# RejsaCAN_v6_0_-_Schematic.net
KiCad netlist of a schematic drawn in EasyEDA
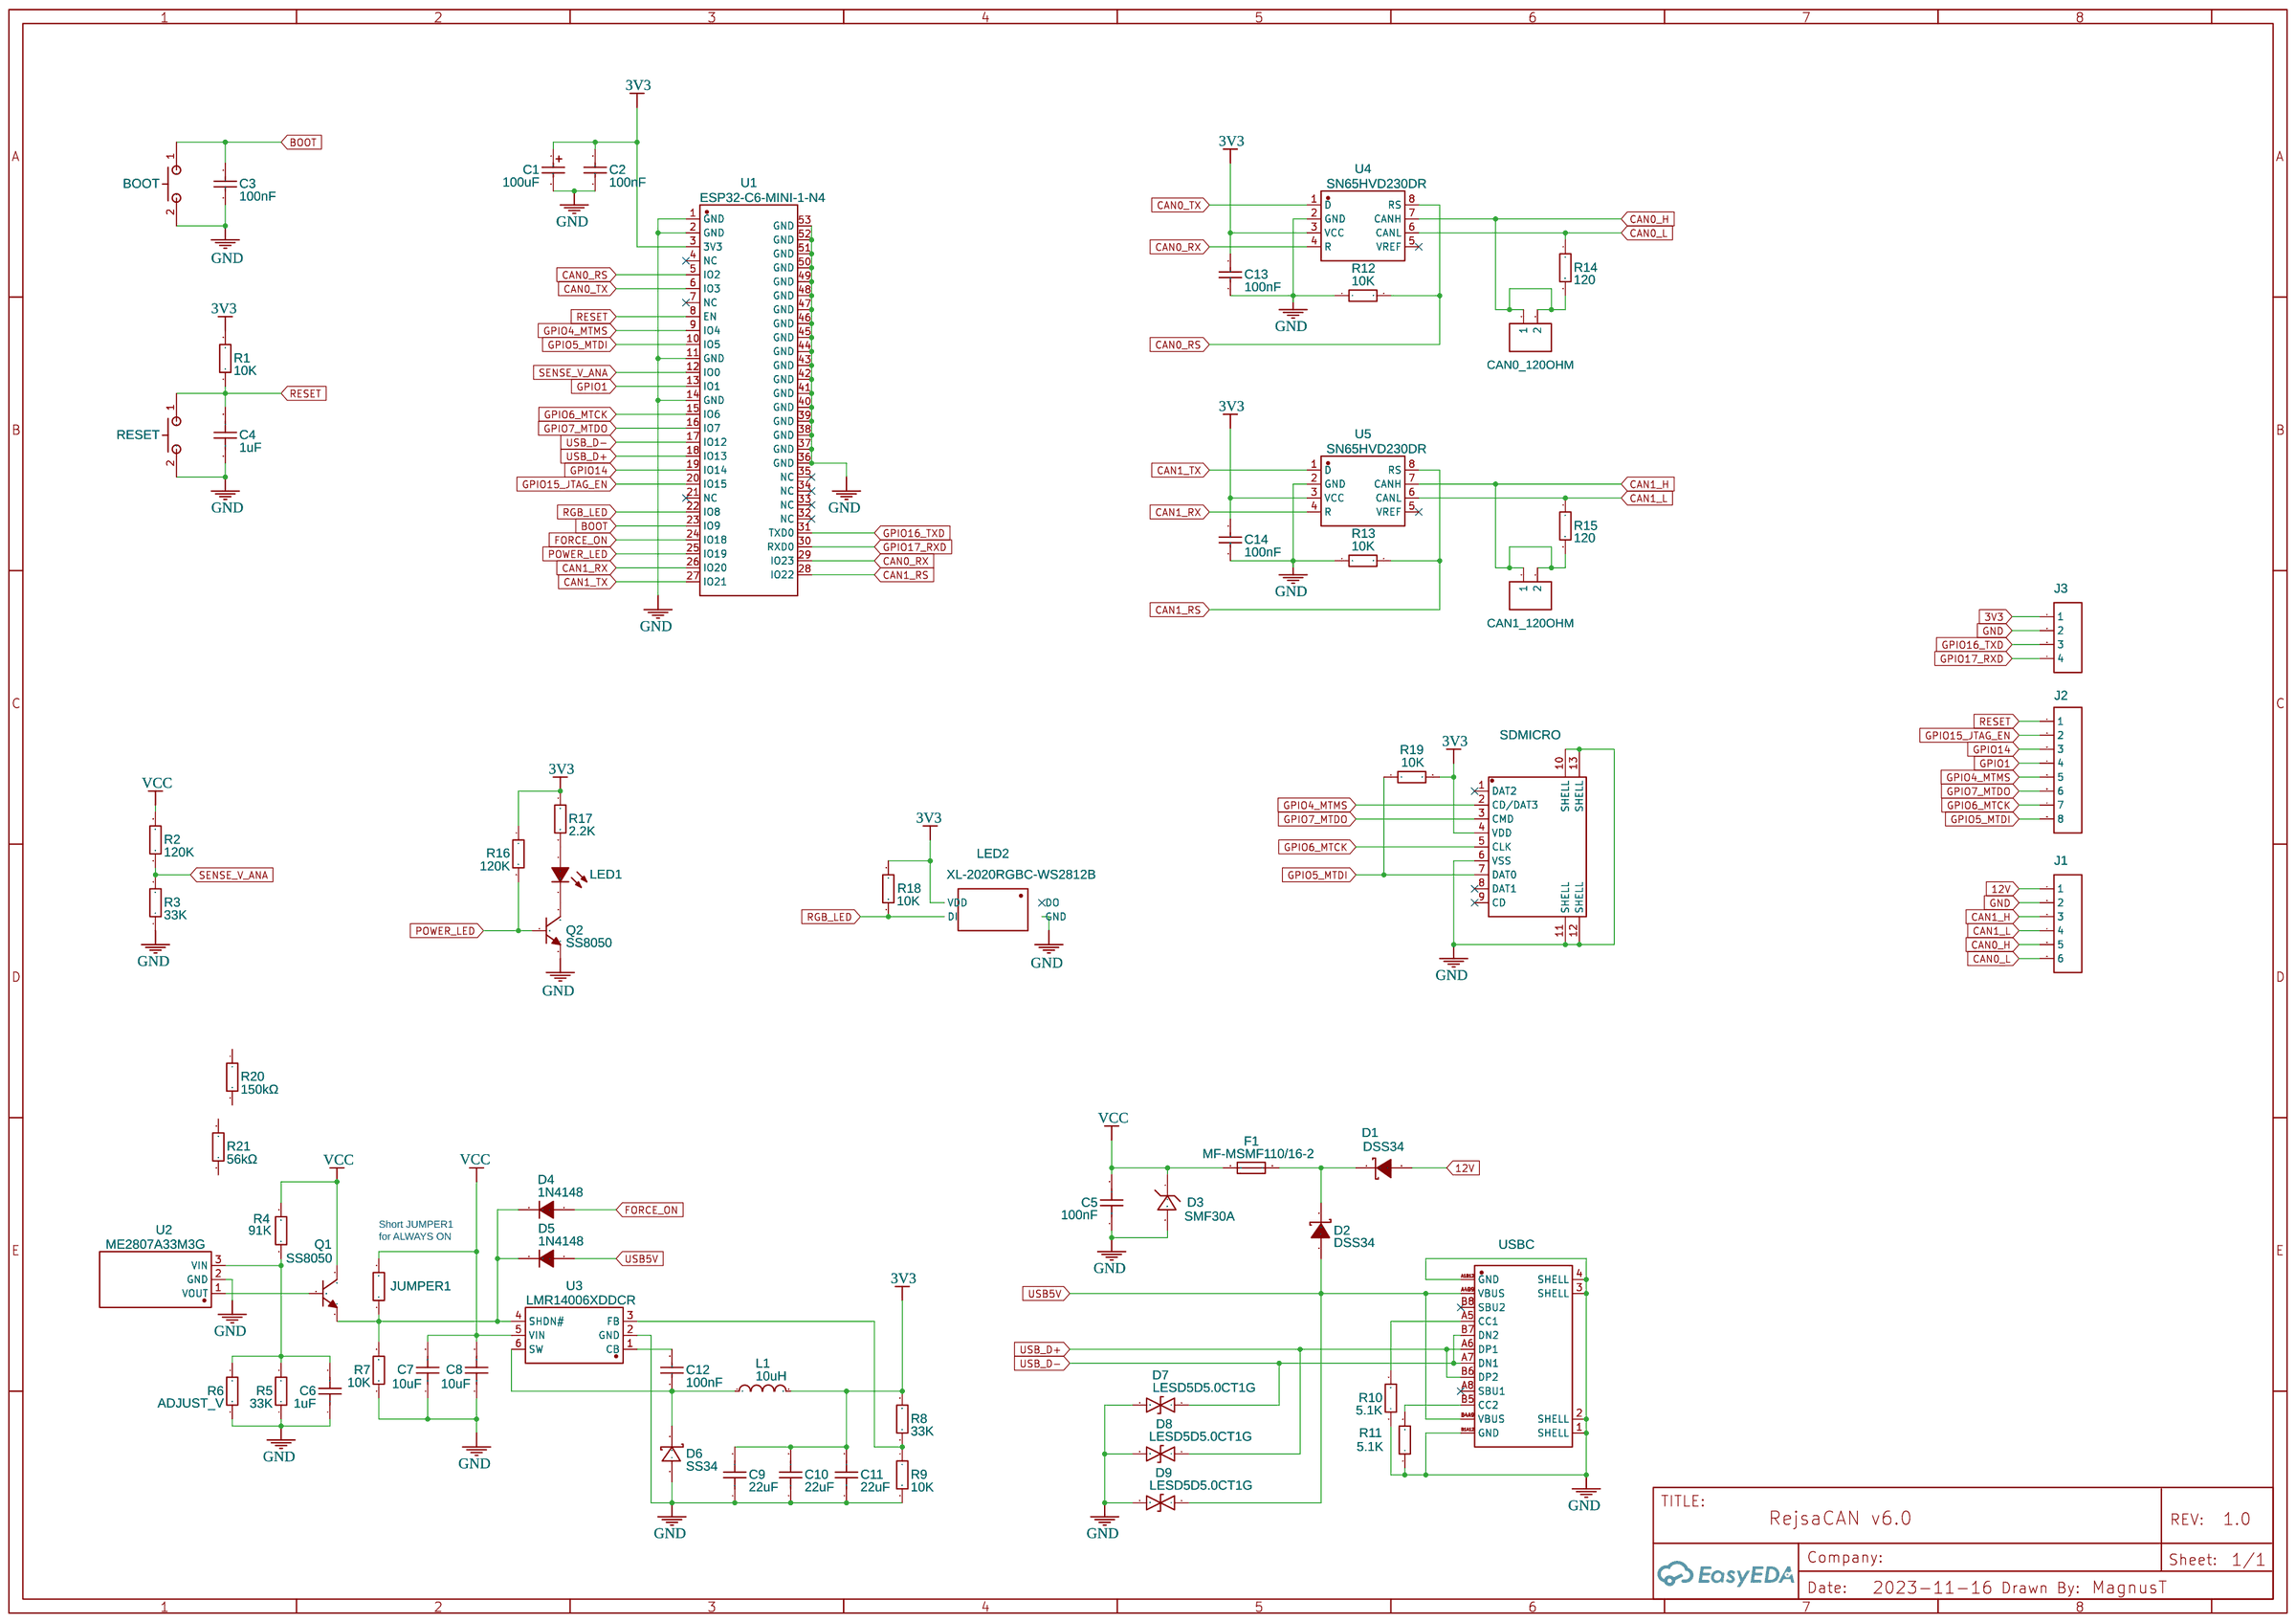
[diagram p0: schematic sheet]

(export (version "E")
  (design (tool "Eeschema 10.0.6"))
  (components
    (comp (ref "BOOT")
      (value "GT-TC029B-H025-L1N")
      (fields (field (name "Manufacturer") "G-Switch"))
      (libsource (lib "") (part "GT-TC029B-H025-L1N_1"))
    )
    (comp (ref "C1")
      (value "100uF")
      (fields (field (name "Manufacturer Part") "TAJB107K006RNJ") (field (name "Manufacturer") "Kyocera AVX"))
      (libsource (lib "") (part "TAJB107K006RNJ"))
    )
    (comp (ref "C2")
      (value "100nF")
      (fields (field (name "Manufacturer Part") "CL05B104KO5NNNC") (field (name "Manufacturer") "SAMSUNG"))
      (libsource (lib "") (part "CL05B104KO5NNNC"))
    )
    (comp (ref "C3")
      (value "100nF")
      (fields (field (name "Manufacturer Part") "CL05B104KO5NNNC") (field (name "Manufacturer") "SAMSUNG"))
      (libsource (lib "") (part "CL05B104KO5NNNC"))
    )
    (comp (ref "C4")
      (value "1uF")
      (fields (field (name "Manufacturer Part") "CL05A105KA5NQNC") (field (name "Manufacturer") "SAMSUNG"))
      (libsource (lib "") (part "CL05A105KA5NQNC_1"))
    )
    (comp (ref "C5")
      (value "100nF")
      (fields
        (field (name "Manufacturer Part") "CL05B104KB54PNC")
        (field (name "Manufacturer") "Samsung Electro-Mechanics")
      )
      (libsource (lib "") (part "CL05B104KB54PNC"))
    )
    (comp (ref "C6")
      (value "1uF")
      (fields (field (name "Manufacturer Part") "CL05A105KA5NQNC") (field (name "Manufacturer") "SAMSUNG"))
      (libsource (lib "") (part "CL05A105KA5NQNC"))
    )
    (comp (ref "C7")
      (value "10uF")
      (fields
        (field (name "Manufacturer Part") "CL21A106KBYQNNE")
        (field (name "Manufacturer") "SAMSUNG(三星)")
      )
      (libsource (lib "") (part "CL21A106KBYQNNE"))
    )
    (comp (ref "C8")
      (value "10uF")
      (fields
        (field (name "Manufacturer Part") "CL21A106KBYQNNE")
        (field (name "Manufacturer") "SAMSUNG(三星)")
      )
      (libsource (lib "") (part "CL21A106KBYQNNE"))
    )
    (comp (ref "C9")
      (value "22uF")
      (fields (field (name "Manufacturer Part") "CL10A226MQ8NRNC") (field (name "Manufacturer") "SAMSUNG"))
      (libsource (lib "") (part "CL10A226MQ8NRNC"))
    )
    (comp (ref "C10")
      (value "22uF")
      (fields (field (name "Manufacturer Part") "CL10A226MQ8NRNC") (field (name "Manufacturer") "SAMSUNG"))
      (libsource (lib "") (part "CL10A226MQ8NRNC"))
    )
    (comp (ref "C11")
      (value "22uF")
      (fields (field (name "Manufacturer Part") "CL10A226MQ8NRNC") (field (name "Manufacturer") "SAMSUNG"))
      (libsource (lib "") (part "CL10A226MQ8NRNC"))
    )
    (comp (ref "C12")
      (value "100nF")
      (fields (field (name "Manufacturer Part") "CL05B104KO5NNNC") (field (name "Manufacturer") "SAMSUNG"))
      (libsource (lib "") (part "CL05B104KO5NNNC"))
    )
    (comp (ref "C13")
      (value "100nF")
      (fields (field (name "Manufacturer Part") "CL05B104KO5NNNC") (field (name "Manufacturer") "SAMSUNG"))
      (libsource (lib "") (part "CL05B104KO5NNNC"))
    )
    (comp (ref "C14")
      (value "100nF")
      (fields (field (name "Manufacturer Part") "CL05B104KO5NNNC") (field (name "Manufacturer") "SAMSUNG"))
      (libsource (lib "") (part "CL05B104KO5NNNC"))
    )
    (comp (ref "CAN0_120OHM") (value "HDR-M-2.54_1x2") (libsource (lib "") (part "HDR-M-2.54_1x2")))
    (comp (ref "CAN1_120OHM") (value "HDR-M-2.54_1x2") (libsource (lib "") (part "HDR-M-2.54_1x2_1")))
    (comp (ref "D1")
      (value "DSS34")
      (fields (field (name "Manufacturer") "STARSEA"))
      (libsource (lib "") (part "DSS34"))
    )
    (comp (ref "D2")
      (value "DSS34")
      (fields (field (name "Manufacturer") "STARSEA"))
      (libsource (lib "") (part "DSS34_1"))
    )
    (comp (ref "D3")
      (value "SMF30A")
      (fields (field (name "Manufacturer") "DOWO"))
      (libsource (lib "") (part "SMF30A_C366558"))
    )
    (comp (ref "D4")
      (value "1N4148")
      (fields (field (name "Manufacturer Part") "1N4148WS T4") (field (name "Manufacturer") "CJ"))
      (libsource (lib "") (part "1N4148WS T4"))
    )
    (comp (ref "D5")
      (value "1N4148")
      (fields (field (name "Manufacturer Part") "1N4148WS T4") (field (name "Manufacturer") "CJ"))
      (libsource (lib "") (part "1N4148WS T4"))
    )
    (comp (ref "D6")
      (value "SS34")
      (fields (field (name "Manufacturer") "MDD"))
      (libsource (lib "") (part "SS34_C8678"))
    )
    (comp (ref "D7")
      (value "LESD5D5.0CT1G")
      (fields (field (name "Manufacturer") "Leshan Radio"))
      (libsource (lib "") (part "LESD5D5.0CT1G"))
    )
    (comp (ref "D8")
      (value "LESD5D5.0CT1G")
      (fields (field (name "Manufacturer") "Leshan Radio"))
      (libsource (lib "") (part "LESD5D5.0CT1G"))
    )
    (comp (ref "D9")
      (value "LESD5D5.0CT1G")
      (fields (field (name "Manufacturer") "Leshan Radio"))
      (libsource (lib "") (part "LESD5D5.0CT1G"))
    )
    (comp (ref "F1")
      (value "MF-MSMF110/16-2")
      (fields (field (name "Manufacturer") "BOURNS"))
      (libsource (lib "") (part "MF-MSMF110/16-2"))
    )
    (comp (ref "J1") (value "HDR-M-2.54_1x6") (libsource (lib "") (part "HDR-M-2.54_1x6")))
    (comp (ref "J2") (value "HDR-M-2.54_1x8") (libsource (lib "") (part "HDR-M-2.54_1x8")))
    (comp (ref "J3") (value "HDR-M-2.54_1x4") (libsource (lib "") (part "HDR-M-2.54_1x4")))
    (comp (ref "JUMPER1") (value "CUT") (libsource (lib "") (part "0402WGF3092TCE")))
    (comp (ref "L1")
      (value "10uH")
      (fields
        (field (name "Manufacturer Part") "SLP6028S100MTT")
        (field (name "Manufacturer") "Sunltech Tech")
      )
      (libsource (lib "") (part "SLP6028S100MTT"))
    )
    (comp (ref "LED1")
      (value "19-217/GHC-YR1S2/3T")
      (fields (field (name "Manufacturer") "EVERLIGHT"))
      (libsource (lib "") (part "19-217/GHC-YR1S2/3T"))
    )
    (comp (ref "LED2")
      (value "XL-2020RGBC-WS2812B")
      (fields (field (name "Manufacturer") "XINGLIGHT(成兴光)"))
      (libsource (lib "") (part "XL-2020RGBC-WS2812B"))
    )
    (comp (ref "Q1")
      (value "SS8050")
      (fields (field (name "Manufacturer") "CJ"))
      (libsource (lib "") (part "SS8050_C2150"))
    )
    (comp (ref "Q2")
      (value "SS8050")
      (fields (field (name "Manufacturer") "CJ"))
      (libsource (lib "") (part "SS8050_C2150"))
    )
    (comp (ref "R1")
      (value "10K")
      (fields (field (name "Manufacturer Part") "0402WGF1002TCE") (field (name "Manufacturer") "UniOhm"))
      (libsource (lib "") (part "0402WGF1002TCE_1"))
    )
    (comp (ref "R2")
      (value "120K")
      (fields (field (name "Manufacturer Part") "0402WGF1203TCE") (field (name "Manufacturer") "UniOhm"))
      (libsource (lib "") (part "0402WGF1203TCE_1"))
    )
    (comp (ref "R3")
      (value "33K")
      (fields (field (name "Manufacturer Part") "0402WGF3302TCE") (field (name "Manufacturer") "UniOhm"))
      (libsource (lib "") (part "0402WGF3302TCE"))
    )
    (comp (ref "R4")
      (value "91K")
      (fields (field (name "Manufacturer Part") "0402WGF9102TCE") (field (name "Manufacturer") "UniOhm"))
      (libsource (lib "") (part "0402WGF9102TCE"))
    )
    (comp (ref "R5")
      (value "33K")
      (fields (field (name "Manufacturer Part") "0402WGF3302TCE") (field (name "Manufacturer") "UniOhm"))
      (libsource (lib "") (part "0402WGF3302TCE"))
    )
    (comp (ref "R6") (value "ADJUST_V") (libsource (lib "") (part "RC0805JR-131KL")))
    (comp (ref "R7")
      (value "10K")
      (fields (field (name "Manufacturer Part") "0402WGF1002TCE") (field (name "Manufacturer") "UniOhm"))
      (libsource (lib "") (part "0402WGF1002TCE_1"))
    )
    (comp (ref "R8")
      (value "33K")
      (fields (field (name "Manufacturer Part") "0402WGF3302TCE") (field (name "Manufacturer") "UniOhm"))
      (libsource (lib "") (part "0402WGF3302TCE"))
    )
    (comp (ref "R9")
      (value "10K")
      (fields (field (name "Manufacturer Part") "0402WGF1002TCE") (field (name "Manufacturer") "UniOhm"))
      (libsource (lib "") (part "0402WGF1002TCE_2"))
    )
    (comp (ref "R10")
      (value "5.1K")
      (fields (field (name "Manufacturer Part") "0402WGF5101TCE") (field (name "Manufacturer") "UniOhm"))
      (libsource (lib "") (part "0402WGF5101TCE"))
    )
    (comp (ref "R11")
      (value "5.1K")
      (fields (field (name "Manufacturer Part") "0402WGF5101TCE") (field (name "Manufacturer") "UniOhm"))
      (libsource (lib "") (part "0402WGF5101TCE"))
    )
    (comp (ref "R12")
      (value "10K")
      (fields (field (name "Manufacturer Part") "0402WGF1002TCE") (field (name "Manufacturer") "UniOhm"))
      (libsource (lib "") (part "0402WGF1002TCE"))
    )
    (comp (ref "R13")
      (value "10K")
      (fields (field (name "Manufacturer Part") "0402WGF1002TCE") (field (name "Manufacturer") "UniOhm"))
      (libsource (lib "") (part "0402WGF1002TCE"))
    )
    (comp (ref "R14")
      (value "120")
      (fields (field (name "Manufacturer Part") "RTT061200FTP") (field (name "Manufacturer") "RALEC"))
      (libsource (lib "") (part "RTT061200FTP"))
    )
    (comp (ref "R15")
      (value "120")
      (fields (field (name "Manufacturer Part") "RTT061200FTP") (field (name "Manufacturer") "RALEC"))
      (libsource (lib "") (part "RTT061200FTP"))
    )
    (comp (ref "R16")
      (value "120K")
      (fields (field (name "Manufacturer Part") "0402WGF1203TCE") (field (name "Manufacturer") "UniOhm"))
      (libsource (lib "") (part "0402WGF1203TCE"))
    )
    (comp (ref "R17")
      (value "2.2K")
      (fields (field (name "Manufacturer Part") "0402WGF2201TCE") (field (name "Manufacturer") "UniOhm"))
      (libsource (lib "") (part "0402WGF2201TCE"))
    )
    (comp (ref "R18")
      (value "10K")
      (fields (field (name "Manufacturer Part") "0402WGF1002TCE") (field (name "Manufacturer") "UniOhm"))
      (libsource (lib "") (part "0402WGF1002TCE_1"))
    )
    (comp (ref "R19")
      (value "10K")
      (fields (field (name "Manufacturer Part") "0402WGF1002TCE") (field (name "Manufacturer") "UniOhm"))
      (libsource (lib "") (part "0402WGF1002TCE"))
    )
    (comp (ref "R20")
      (value "150kΩ")
      (fields
        (field (name "Manufacturer Part") "0402WGF1503TCE")
        (field (name "Manufacturer") "UNI-ROYAL(厚声)")
      )
      (libsource (lib "") (part "0402WGF1503TCE"))
    )
    (comp (ref "R21")
      (value "56kΩ")
      (fields
        (field (name "Manufacturer Part") "0402WGF5602TCE")
        (field (name "Manufacturer") "UNI-ROYAL(厚声)")
      )
      (libsource (lib "") (part "0402WGF5602TCE"))
    )
    (comp (ref "RESET")
      (value "GT-TC029B-H025-L1N")
      (fields (field (name "Manufacturer") "G-Switch"))
      (libsource (lib "") (part "GT-TC029B-H025-L1N"))
    )
    (comp (ref "SDMICRO")
      (value "TF-115")
      (fields (field (name "Manufacturer") "XUNPU(讯普)"))
      (libsource (lib "") (part "TF-115"))
    )
    (comp (ref "U1")
      (value "ESP32-C6-MINI-1-N4")
      (fields (field (name "Manufacturer") "ESPRESSIF(乐鑫)"))
      (libsource (lib "") (part "ESP32-C3-MINI-1-H4(4MB)"))
    )
    (comp (ref "U2")
      (value "ME2807A33M3G")
      (fields (field (name "Manufacturer") "Nanjing Micro One Elec"))
      (libsource (lib "") (part "ME2807A33M3G"))
    )
    (comp (ref "U3")
      (value "LMR14006XDDCR")
      (fields (field (name "Manufacturer") "Texas Instruments"))
      (libsource (lib "") (part "LMR14006XDDCR"))
    )
    (comp (ref "U4")
      (value "SN65HVD230DR")
      (fields (field (name "Manufacturer") "TI"))
      (libsource (lib "") (part "SN65HVD230DR"))
    )
    (comp (ref "U5")
      (value "SN65HVD230DR")
      (fields (field (name "Manufacturer") "TI"))
      (libsource (lib "") (part "SN65HVD230DR"))
    )
    (comp (ref "USBC")
      (value "GT-USB-7010ASV")
      (fields (field (name "Manufacturer") "G-Switch(品赞)"))
      (libsource (lib "") (part "GT-USB-7010ASV"))
    )
  )
  (nets
    (net (code "1") (name "3V3") (class "Default")
      (node (ref "C1") (pin "1") (pinfunction "1_1") (pintype "input"))
      (node (ref "C10") (pin "2") (pinfunction "2_2") (pintype "unspecified"))
      (node (ref "C11") (pin "2") (pinfunction "2_2") (pintype "unspecified"))
      (node (ref "C13") (pin "2") (pinfunction "2_2") (pintype "input"))
      (node (ref "C14") (pin "2") (pinfunction "2_2") (pintype "input"))
      (node (ref "C2") (pin "2") (pinfunction "2_2") (pintype "input"))
      (node (ref "C9") (pin "2") (pinfunction "2_2") (pintype "unspecified"))
      (node (ref "J3") (pin "1") (pinfunction "1_1") (pintype "unspecified"))
      (node (ref "L1") (pin "2") (pinfunction "2_2") (pintype "unspecified"))
      (node (ref "LED2") (pin "4") (pinfunction "VDD_4") (pintype "unspecified"))
      (node (ref "R1") (pin "2") (pinfunction "2_2") (pintype "input"))
      (node (ref "R16") (pin "1") (pinfunction "1_1") (pintype "input"))
      (node (ref "R17") (pin "1") (pinfunction "1_1") (pintype "input"))
      (node (ref "R18") (pin "2") (pinfunction "2_2") (pintype "input"))
      (node (ref "R19") (pin "2") (pinfunction "2_2") (pintype "input"))
      (node (ref "R8") (pin "2") (pinfunction "2_2") (pintype "input"))
      (node (ref "SDMICRO") (pin "4") (pinfunction "VDD_4") (pintype "unspecified"))
      (node (ref "U1") (pin "3") (pinfunction "3V3_3") (pintype "unspecified"))
      (node (ref "U4") (pin "3") (pinfunction "VCC_3") (pintype "unspecified"))
      (node (ref "U5") (pin "3") (pinfunction "VCC_3") (pintype "unspecified"))
    )
    (net (code "2") (name "12V") (class "Default")
      (node (ref "D1") (pin "2") (pinfunction "A_2") (pintype "unspecified"))
      (node (ref "J1") (pin "1") (pinfunction "1_1") (pintype "input"))
    )
    (net (code "3") (name "BOOT") (class "Default")
      (node (ref "BOOT") (pin "1") (pinfunction "1_1") (pintype "unspecified"))
      (node (ref "C3") (pin "2") (pinfunction "2_2") (pintype "input"))
      (node (ref "U1") (pin "23") (pinfunction "IO9_23") (pintype "unspecified"))
    )
    (net (code "4") (name "CAN0_H") (class "Default")
      (node (ref "CAN0_120OHM") (pin "1") (pinfunction "1_1") (pintype "unspecified"))
      (node (ref "CAN0_120OHM") (pin "2") (pinfunction "2_2") (pintype "unspecified"))
      (node (ref "J1") (pin "5") (pinfunction "5_5") (pintype "input"))
      (node (ref "R14") (pin "2") (pinfunction "2_2") (pintype "unspecified"))
      (node (ref "U4") (pin "7") (pinfunction "CANH_7") (pintype "unspecified"))
    )
    (net (code "5") (name "CAN0_L") (class "Default")
      (node (ref "J1") (pin "6") (pinfunction "6_6") (pintype "input"))
      (node (ref "R14") (pin "1") (pinfunction "1_1") (pintype "unspecified"))
      (node (ref "U4") (pin "6") (pinfunction "CANL_6") (pintype "unspecified"))
    )
    (net (code "6") (name "CAN0_RS") (class "Default")
      (node (ref "R12") (pin "2") (pinfunction "2_2") (pintype "input"))
      (node (ref "U1") (pin "5") (pinfunction "IO2_5") (pintype "unspecified"))
      (node (ref "U4") (pin "8") (pinfunction "RS_8") (pintype "unspecified"))
    )
    (net (code "7") (name "CAN0_RX") (class "Default")
      (node (ref "U1") (pin "29") (pinfunction "IO23_29") (pintype "unspecified"))
      (node (ref "U4") (pin "4") (pinfunction "R_4") (pintype "unspecified"))
    )
    (net (code "8") (name "CAN0_TX") (class "Default")
      (node (ref "U1") (pin "6") (pinfunction "IO3_6") (pintype "unspecified"))
      (node (ref "U4") (pin "1") (pinfunction "D_1") (pintype "unspecified"))
    )
    (net (code "9") (name "CAN1_H") (class "Default")
      (node (ref "CAN1_120OHM") (pin "1") (pinfunction "1_1") (pintype "unspecified"))
      (node (ref "CAN1_120OHM") (pin "2") (pinfunction "2_2") (pintype "unspecified"))
      (node (ref "J1") (pin "3") (pinfunction "3_3") (pintype "input"))
      (node (ref "R15") (pin "2") (pinfunction "2_2") (pintype "unspecified"))
      (node (ref "U5") (pin "7") (pinfunction "CANH_7") (pintype "unspecified"))
    )
    (net (code "10") (name "CAN1_L") (class "Default")
      (node (ref "J1") (pin "4") (pinfunction "4_4") (pintype "input"))
      (node (ref "R15") (pin "1") (pinfunction "1_1") (pintype "unspecified"))
      (node (ref "U5") (pin "6") (pinfunction "CANL_6") (pintype "unspecified"))
    )
    (net (code "11") (name "CAN1_RS") (class "Default")
      (node (ref "R13") (pin "2") (pinfunction "2_2") (pintype "input"))
      (node (ref "U1") (pin "28") (pinfunction "IO22_28") (pintype "unspecified"))
      (node (ref "U5") (pin "8") (pinfunction "RS_8") (pintype "unspecified"))
    )
    (net (code "12") (name "CAN1_RX") (class "Default")
      (node (ref "U1") (pin "26") (pinfunction "IO20_26") (pintype "unspecified"))
      (node (ref "U5") (pin "4") (pinfunction "R_4") (pintype "unspecified"))
    )
    (net (code "13") (name "CAN1_TX") (class "Default")
      (node (ref "U1") (pin "27") (pinfunction "IO21_27") (pintype "unspecified"))
      (node (ref "U5") (pin "1") (pinfunction "D_1") (pintype "unspecified"))
    )
    (net (code "14") (name "FORCE_ON") (class "Default")
      (node (ref "D4") (pin "2") (pinfunction "A_2") (pintype "unspecified"))
      (node (ref "U1") (pin "24") (pinfunction "IO18_24") (pintype "unspecified"))
    )
    (net (code "15") (name "GND") (class "Default")
      (node (ref "BOOT") (pin "2") (pinfunction "2_2") (pintype "unspecified"))
      (node (ref "C1") (pin "2") (pinfunction "2_2") (pintype "input"))
      (node (ref "C10") (pin "1") (pinfunction "1_1") (pintype "unspecified"))
      (node (ref "C11") (pin "1") (pinfunction "1_1") (pintype "unspecified"))
      (node (ref "C13") (pin "1") (pinfunction "1_1") (pintype "input"))
      (node (ref "C14") (pin "1") (pinfunction "1_1") (pintype "input"))
      (node (ref "C2") (pin "1") (pinfunction "1_1") (pintype "input"))
      (node (ref "C3") (pin "1") (pinfunction "1_1") (pintype "input"))
      (node (ref "C4") (pin "1") (pinfunction "1_1") (pintype "unspecified"))
      (node (ref "C5") (pin "1") (pinfunction "1_1") (pintype "unspecified"))
      (node (ref "C6") (pin "1") (pinfunction "1_1") (pintype "unspecified"))
      (node (ref "C7") (pin "1") (pinfunction "1_1") (pintype "unspecified"))
      (node (ref "C8") (pin "1") (pinfunction "1_1") (pintype "unspecified"))
      (node (ref "C9") (pin "1") (pinfunction "1_1") (pintype "unspecified"))
      (node (ref "D3") (pin "2") (pinfunction "2_2") (pintype "unspecified"))
      (node (ref "D6") (pin "2") (pinfunction "A_2") (pintype "unspecified"))
      (node (ref "D7") (pin "2") (pinfunction "2_2") (pintype "unspecified"))
      (node (ref "D8") (pin "2") (pinfunction "2_2") (pintype "unspecified"))
      (node (ref "D9") (pin "2") (pinfunction "2_2") (pintype "unspecified"))
      (node (ref "J1") (pin "2") (pinfunction "2_2") (pintype "input"))
      (node (ref "J3") (pin "2") (pinfunction "2_2") (pintype "unspecified"))
      (node (ref "LED2") (pin "2") (pinfunction "GND_2") (pintype "unspecified"))
      (node (ref "Q2") (pin "2") (pinfunction "E_2") (pintype "unspecified"))
      (node (ref "R10") (pin "1") (pinfunction "1_1") (pintype "input"))
      (node (ref "R11") (pin "1") (pinfunction "1_1") (pintype "input"))
      (node (ref "R12") (pin "1") (pinfunction "1_1") (pintype "input"))
      (node (ref "R13") (pin "1") (pinfunction "1_1") (pintype "input"))
      (node (ref "R3") (pin "1") (pinfunction "1_1") (pintype "input"))
      (node (ref "R5") (pin "1") (pinfunction "1_1") (pintype "input"))
      (node (ref "R6") (pin "2") (pinfunction "2_2") (pintype "unspecified"))
      (node (ref "R7") (pin "1") (pinfunction "1_1") (pintype "input"))
      (node (ref "R9") (pin "2") (pinfunction "2_2") (pintype "input"))
      (node (ref "RESET") (pin "2") (pinfunction "2_2") (pintype "unspecified"))
      (node (ref "SDMICRO") (pin "10") (pinfunction "SHELL_10") (pintype "unspecified"))
      (node (ref "SDMICRO") (pin "11") (pinfunction "SHELL_11") (pintype "unspecified"))
      (node (ref "SDMICRO") (pin "12") (pinfunction "SHELL_12") (pintype "unspecified"))
      (node (ref "SDMICRO") (pin "13") (pinfunction "SHELL_13") (pintype "unspecified"))
      (node (ref "SDMICRO") (pin "6") (pinfunction "VSS_6") (pintype "unspecified"))
      (node (ref "U1") (pin "1") (pinfunction "GND_1") (pintype "unspecified"))
      (node (ref "U1") (pin "11") (pinfunction "GND_11") (pintype "unspecified"))
      (node (ref "U1") (pin "14") (pinfunction "GND_14") (pintype "unspecified"))
      (node (ref "U1") (pin "2") (pinfunction "GND_2") (pintype "unspecified"))
      (node (ref "U1") (pin "36") (pinfunction "GND_36") (pintype "unspecified"))
      (node (ref "U1") (pin "37") (pinfunction "GND_37") (pintype "unspecified"))
      (node (ref "U1") (pin "38") (pinfunction "GND_38") (pintype "unspecified"))
      (node (ref "U1") (pin "39") (pinfunction "GND_39") (pintype "unspecified"))
      (node (ref "U1") (pin "40") (pinfunction "GND_40") (pintype "unspecified"))
      (node (ref "U1") (pin "41") (pinfunction "GND_41") (pintype "unspecified"))
      (node (ref "U1") (pin "42") (pinfunction "GND_42") (pintype "unspecified"))
      (node (ref "U1") (pin "43") (pinfunction "GND_43") (pintype "unspecified"))
      (node (ref "U1") (pin "44") (pinfunction "GND_44") (pintype "unspecified"))
      (node (ref "U1") (pin "45") (pinfunction "GND_45") (pintype "unspecified"))
      (node (ref "U1") (pin "46") (pinfunction "GND_46") (pintype "unspecified"))
      (node (ref "U1") (pin "47") (pinfunction "GND_47") (pintype "unspecified"))
      (node (ref "U1") (pin "48") (pinfunction "GND_48") (pintype "unspecified"))
      (node (ref "U1") (pin "49") (pinfunction "GND_49") (pintype "unspecified"))
      (node (ref "U1") (pin "50") (pinfunction "GND_50") (pintype "unspecified"))
      (node (ref "U1") (pin "51") (pinfunction "GND_51") (pintype "unspecified"))
      (node (ref "U1") (pin "52") (pinfunction "GND_52") (pintype "unspecified"))
      (node (ref "U1") (pin "53") (pinfunction "GND_53") (pintype "unspecified"))
      (node (ref "U2") (pin "2") (pinfunction "GND_2") (pintype "unspecified"))
      (node (ref "U3") (pin "2") (pinfunction "GND_2") (pintype "unspecified"))
      (node (ref "U4") (pin "2") (pinfunction "GND_2") (pintype "unspecified"))
      (node (ref "U5") (pin "2") (pinfunction "GND_2") (pintype "unspecified"))
      (node (ref "USBC") (pin "1") (pinfunction "SHELL_1") (pintype "unspecified"))
      (node (ref "USBC") (pin "2") (pinfunction "SHELL_2") (pintype "unspecified"))
      (node (ref "USBC") (pin "3") (pinfunction "SHELL_3") (pintype "unspecified"))
      (node (ref "USBC") (pin "4") (pinfunction "SHELL_4") (pintype "unspecified"))
      (node (ref "USBC") (pin "A1B12") (pinfunction "GND_A1B12") (pintype "unspecified"))
      (node (ref "USBC") (pin "B1A12") (pinfunction "GND_B1A12") (pintype "unspecified"))
    )
    (net (code "16") (name "GPIO1") (class "Default")
      (node (ref "J2") (pin "4") (pinfunction "4_4") (pintype "unspecified"))
      (node (ref "U1") (pin "13") (pinfunction "IO1_13") (pintype "unspecified"))
    )
    (net (code "17") (name "GPIO4_MTMS") (class "Default")
      (node (ref "J2") (pin "5") (pinfunction "5_5") (pintype "unspecified"))
      (node (ref "SDMICRO") (pin "2") (pinfunction "CD/DAT3_2") (pintype "unspecified"))
      (node (ref "U1") (pin "9") (pinfunction "IO4_9") (pintype "unspecified"))
    )
    (net (code "18") (name "GPIO5_MTDI") (class "Default")
      (node (ref "J2") (pin "8") (pinfunction "8_8") (pintype "unspecified"))
      (node (ref "R19") (pin "1") (pinfunction "1_1") (pintype "input"))
      (node (ref "SDMICRO") (pin "7") (pinfunction "DAT0_7") (pintype "unspecified"))
      (node (ref "U1") (pin "10") (pinfunction "IO5_10") (pintype "unspecified"))
    )
    (net (code "19") (name "GPIO6_MTCK") (class "Default")
      (node (ref "J2") (pin "7") (pinfunction "7_7") (pintype "unspecified"))
      (node (ref "SDMICRO") (pin "5") (pinfunction "CLK_5") (pintype "unspecified"))
      (node (ref "U1") (pin "15") (pinfunction "IO6_15") (pintype "unspecified"))
    )
    (net (code "20") (name "GPIO7_MTDO") (class "Default")
      (node (ref "J2") (pin "6") (pinfunction "6_6") (pintype "unspecified"))
      (node (ref "SDMICRO") (pin "3") (pinfunction "CMD_3") (pintype "unspecified"))
      (node (ref "U1") (pin "16") (pinfunction "IO7_16") (pintype "unspecified"))
    )
    (net (code "21") (name "GPIO14") (class "Default")
      (node (ref "J2") (pin "3") (pinfunction "3_3") (pintype "unspecified"))
      (node (ref "U1") (pin "19") (pinfunction "IO14_19") (pintype "unspecified"))
    )
    (net (code "22") (name "GPIO15_JTAG_EN") (class "Default")
      (node (ref "J2") (pin "2") (pinfunction "2_2") (pintype "unspecified"))
      (node (ref "U1") (pin "20") (pinfunction "IO15_20") (pintype "unspecified"))
    )
    (net (code "23") (name "GPIO16_TXD") (class "Default")
      (node (ref "J3") (pin "3") (pinfunction "3_3") (pintype "unspecified"))
      (node (ref "U1") (pin "31") (pinfunction "TXD0_31") (pintype "unspecified"))
    )
    (net (code "24") (name "GPIO17_RXD") (class "Default")
      (node (ref "J3") (pin "4") (pinfunction "4_4") (pintype "unspecified"))
      (node (ref "U1") (pin "30") (pinfunction "RXD0_30") (pintype "unspecified"))
    )
    (net (code "25") (name "Net-(D1-K)") (class "Default")
      (node (ref "D1") (pin "1") (pinfunction "K_1") (pintype "unspecified"))
      (node (ref "D2") (pin "1") (pinfunction "K_1") (pintype "unspecified"))
      (node (ref "F1") (pin "2") (pinfunction "2_2") (pintype "unspecified"))
    )
    (net (code "26") (name "Net-(D4-K)") (class "Default")
      (node (ref "D4") (pin "1") (pinfunction "K_1") (pintype "unspecified"))
      (node (ref "D5") (pin "1") (pinfunction "K_1") (pintype "unspecified"))
      (node (ref "JUMPER1") (pin "1") (pinfunction "1_1") (pintype "unspecified"))
      (node (ref "Q1") (pin "2") (pinfunction "E_2") (pintype "unspecified"))
      (node (ref "R7") (pin "2") (pinfunction "2_2") (pintype "input"))
      (node (ref "U3") (pin "4") (pinfunction "SHDN#_4") (pintype "unspecified"))
    )
    (net (code "27") (name "Net-(D6-K)") (class "Default")
      (node (ref "C12") (pin "1") (pinfunction "1_1") (pintype "input"))
      (node (ref "D6") (pin "1") (pinfunction "K_1") (pintype "unspecified"))
      (node (ref "L1") (pin "1") (pinfunction "1_1") (pintype "unspecified"))
      (node (ref "U3") (pin "6") (pinfunction "SW_6") (pintype "unspecified"))
    )
    (net (code "28") (name "Net-(LED1-A)") (class "Default")
      (node (ref "LED1") (pin "1") (pinfunction "A_1") (pintype "input"))
      (node (ref "R17") (pin "2") (pinfunction "2_2") (pintype "input"))
    )
    (net (code "29") (name "Net-(LED1-C)") (class "Default")
      (node (ref "LED1") (pin "2") (pinfunction "C_2") (pintype "input"))
      (node (ref "Q2") (pin "3") (pinfunction "C_3") (pintype "unspecified"))
    )
    (net (code "30") (name "Net-(Q1-B)") (class "Default")
      (node (ref "Q1") (pin "1") (pinfunction "B_1") (pintype "unspecified"))
      (node (ref "U2") (pin "1") (pinfunction "VOUT_1") (pintype "unspecified"))
    )
    (net (code "31") (name "Net-(U2-VIN)") (class "Default")
      (node (ref "C6") (pin "2") (pinfunction "2_2") (pintype "unspecified"))
      (node (ref "R4") (pin "1") (pinfunction "1_1") (pintype "input"))
      (node (ref "R5") (pin "2") (pinfunction "2_2") (pintype "input"))
      (node (ref "R6") (pin "1") (pinfunction "1_1") (pintype "unspecified"))
      (node (ref "U2") (pin "3") (pinfunction "VIN_3") (pintype "unspecified"))
    )
    (net (code "32") (name "Net-(U3-CB)") (class "Default")
      (node (ref "C12") (pin "2") (pinfunction "2_2") (pintype "input"))
      (node (ref "U3") (pin "1") (pinfunction "CB_1") (pintype "unspecified"))
    )
    (net (code "33") (name "Net-(U3-FB)") (class "Default")
      (node (ref "R8") (pin "1") (pinfunction "1_1") (pintype "input"))
      (node (ref "R9") (pin "1") (pinfunction "1_1") (pintype "input"))
      (node (ref "U3") (pin "3") (pinfunction "FB_3") (pintype "unspecified"))
    )
    (net (code "34") (name "Net-(USBC-CC1)") (class "Default")
      (node (ref "R10") (pin "2") (pinfunction "2_2") (pintype "input"))
      (node (ref "USBC") (pin "A5") (pinfunction "CC1_A5") (pintype "unspecified"))
    )
    (net (code "35") (name "Net-(USBC-CC2)") (class "Default")
      (node (ref "R11") (pin "2") (pinfunction "2_2") (pintype "input"))
      (node (ref "USBC") (pin "B5") (pinfunction "CC2_B5") (pintype "unspecified"))
    )
    (net (code "36") (name "POWER_LED") (class "Default")
      (node (ref "Q2") (pin "1") (pinfunction "B_1") (pintype "unspecified"))
      (node (ref "R16") (pin "2") (pinfunction "2_2") (pintype "input"))
      (node (ref "U1") (pin "25") (pinfunction "IO19_25") (pintype "unspecified"))
    )
    (net (code "37") (name "RESET") (class "Default")
      (node (ref "C4") (pin "2") (pinfunction "2_2") (pintype "unspecified"))
      (node (ref "J2") (pin "1") (pinfunction "1_1") (pintype "unspecified"))
      (node (ref "R1") (pin "1") (pinfunction "1_1") (pintype "input"))
      (node (ref "RESET") (pin "1") (pinfunction "1_1") (pintype "unspecified"))
      (node (ref "U1") (pin "8") (pinfunction "EN_8") (pintype "unspecified"))
    )
    (net (code "38") (name "RGB_LED") (class "Default")
      (node (ref "LED2") (pin "3") (pinfunction "DI_3") (pintype "unspecified"))
      (node (ref "R18") (pin "1") (pinfunction "1_1") (pintype "input"))
      (node (ref "U1") (pin "22") (pinfunction "IO8_22") (pintype "unspecified"))
    )
    (net (code "39") (name "SENSE_V_ANA") (class "Default")
      (node (ref "R2") (pin "1") (pinfunction "1_1") (pintype "input"))
      (node (ref "R3") (pin "2") (pinfunction "2_2") (pintype "input"))
      (node (ref "U1") (pin "12") (pinfunction "IO0_12") (pintype "unspecified"))
    )
    (net (code "40") (name "USB5V") (class "Default")
      (node (ref "D2") (pin "2") (pinfunction "A_2") (pintype "unspecified"))
      (node (ref "D5") (pin "2") (pinfunction "A_2") (pintype "unspecified"))
      (node (ref "D9") (pin "1") (pinfunction "1_1") (pintype "unspecified"))
      (node (ref "USBC") (pin "A4B9") (pinfunction "VBUS_A4B9") (pintype "unspecified"))
      (node (ref "USBC") (pin "B4A9") (pinfunction "VBUS_B4A9") (pintype "unspecified"))
    )
    (net (code "41") (name "USB_D+") (class "Default")
      (node (ref "D8") (pin "1") (pinfunction "1_1") (pintype "unspecified"))
      (node (ref "U1") (pin "18") (pinfunction "IO13_18") (pintype "unspecified"))
      (node (ref "USBC") (pin "A6") (pinfunction "DP1_A6") (pintype "unspecified"))
      (node (ref "USBC") (pin "B6") (pinfunction "DP2_B6") (pintype "unspecified"))
    )
    (net (code "42") (name "USB_D-") (class "Default")
      (node (ref "D7") (pin "1") (pinfunction "1_1") (pintype "unspecified"))
      (node (ref "U1") (pin "17") (pinfunction "IO12_17") (pintype "unspecified"))
      (node (ref "USBC") (pin "A7") (pinfunction "DN1_A7") (pintype "unspecified"))
      (node (ref "USBC") (pin "B7") (pinfunction "DN2_B7") (pintype "unspecified"))
    )
    (net (code "43") (name "VCC") (class "Default")
      (node (ref "C5") (pin "2") (pinfunction "2_2") (pintype "unspecified"))
      (node (ref "C7") (pin "2") (pinfunction "2_2") (pintype "unspecified"))
      (node (ref "C8") (pin "2") (pinfunction "2_2") (pintype "unspecified"))
      (node (ref "D3") (pin "1") (pinfunction "1_1") (pintype "unspecified"))
      (node (ref "F1") (pin "1") (pinfunction "1_1") (pintype "unspecified"))
      (node (ref "JUMPER1") (pin "2") (pinfunction "2_2") (pintype "unspecified"))
      (node (ref "Q1") (pin "3") (pinfunction "C_3") (pintype "unspecified"))
      (node (ref "R2") (pin "2") (pinfunction "2_2") (pintype "input"))
      (node (ref "R4") (pin "2") (pinfunction "2_2") (pintype "input"))
      (node (ref "U3") (pin "5") (pinfunction "VIN_5") (pintype "unspecified"))
    )
    (net (code "44") (name "unconnected-(LED2-DO-Pad1)") (class "Default")
      (node (ref "LED2") (pin "1") (pinfunction "DO_1") (pintype "unspecified+no_connect"))
    )
    (net (code "45") (name "unconnected-(R20-Pad1)") (class "Default")
      (node (ref "R20") (pin "1") (pinfunction "1_1") (pintype "input"))
    )
    (net (code "46") (name "unconnected-(R20-Pad2)") (class "Default")
      (node (ref "R20") (pin "2") (pinfunction "2_2") (pintype "input"))
    )
    (net (code "47") (name "unconnected-(R21-Pad1)") (class "Default")
      (node (ref "R21") (pin "1") (pinfunction "1_1") (pintype "input"))
    )
    (net (code "48") (name "unconnected-(R21-Pad2)") (class "Default")
      (node (ref "R21") (pin "2") (pinfunction "2_2") (pintype "input"))
    )
    (net (code "49") (name "unconnected-(SDMICRO-CD-Pad9)") (class "Default")
      (node (ref "SDMICRO") (pin "9") (pinfunction "CD_9") (pintype "unspecified+no_connect"))
    )
    (net (code "50") (name "unconnected-(SDMICRO-DAT1-Pad8)") (class "Default")
      (node (ref "SDMICRO") (pin "8") (pinfunction "DAT1_8") (pintype "unspecified+no_connect"))
    )
    (net (code "51") (name "unconnected-(SDMICRO-DAT2-Pad1)") (class "Default")
      (node (ref "SDMICRO") (pin "1") (pinfunction "DAT2_1") (pintype "unspecified+no_connect"))
    )
    (net (code "52") (name "unconnected-(U1-NC-Pad4)") (class "Default")
      (node (ref "U1") (pin "4") (pinfunction "NC_4") (pintype "unspecified+no_connect"))
    )
    (net (code "53") (name "unconnected-(U1-NC-Pad7)") (class "Default")
      (node (ref "U1") (pin "7") (pinfunction "NC_7") (pintype "unspecified+no_connect"))
    )
    (net (code "54") (name "unconnected-(U1-NC-Pad21)") (class "Default")
      (node (ref "U1") (pin "21") (pinfunction "NC_21") (pintype "unspecified+no_connect"))
    )
    (net (code "55") (name "unconnected-(U1-NC-Pad32)") (class "Default")
      (node (ref "U1") (pin "32") (pinfunction "NC_32") (pintype "unspecified+no_connect"))
    )
    (net (code "56") (name "unconnected-(U1-NC-Pad33)") (class "Default")
      (node (ref "U1") (pin "33") (pinfunction "NC_33") (pintype "unspecified+no_connect"))
    )
    (net (code "57") (name "unconnected-(U1-NC-Pad34)") (class "Default")
      (node (ref "U1") (pin "34") (pinfunction "NC_34") (pintype "unspecified+no_connect"))
    )
    (net (code "58") (name "unconnected-(U1-NC-Pad35)") (class "Default")
      (node (ref "U1") (pin "35") (pinfunction "NC_35") (pintype "unspecified+no_connect"))
    )
    (net (code "59") (name "unconnected-(U4-VREF-Pad5)") (class "Default")
      (node (ref "U4") (pin "5") (pinfunction "VREF_5") (pintype "unspecified+no_connect"))
    )
    (net (code "60") (name "unconnected-(U5-VREF-Pad5)") (class "Default")
      (node (ref "U5") (pin "5") (pinfunction "VREF_5") (pintype "unspecified+no_connect"))
    )
    (net (code "61") (name "unconnected-(USBC-SBU1-PadA8)") (class "Default")
      (node (ref "USBC") (pin "A8") (pinfunction "SBU1_A8") (pintype "unspecified+no_connect"))
    )
    (net (code "62") (name "unconnected-(USBC-SBU2-PadB8)") (class "Default")
      (node (ref "USBC") (pin "B8") (pinfunction "SBU2_B8") (pintype "unspecified+no_connect"))
    )
  )
)
